# 8x8_LED_Cathode_Base_V4.net
KiCad netlist of a schematic drawn in EAGLE
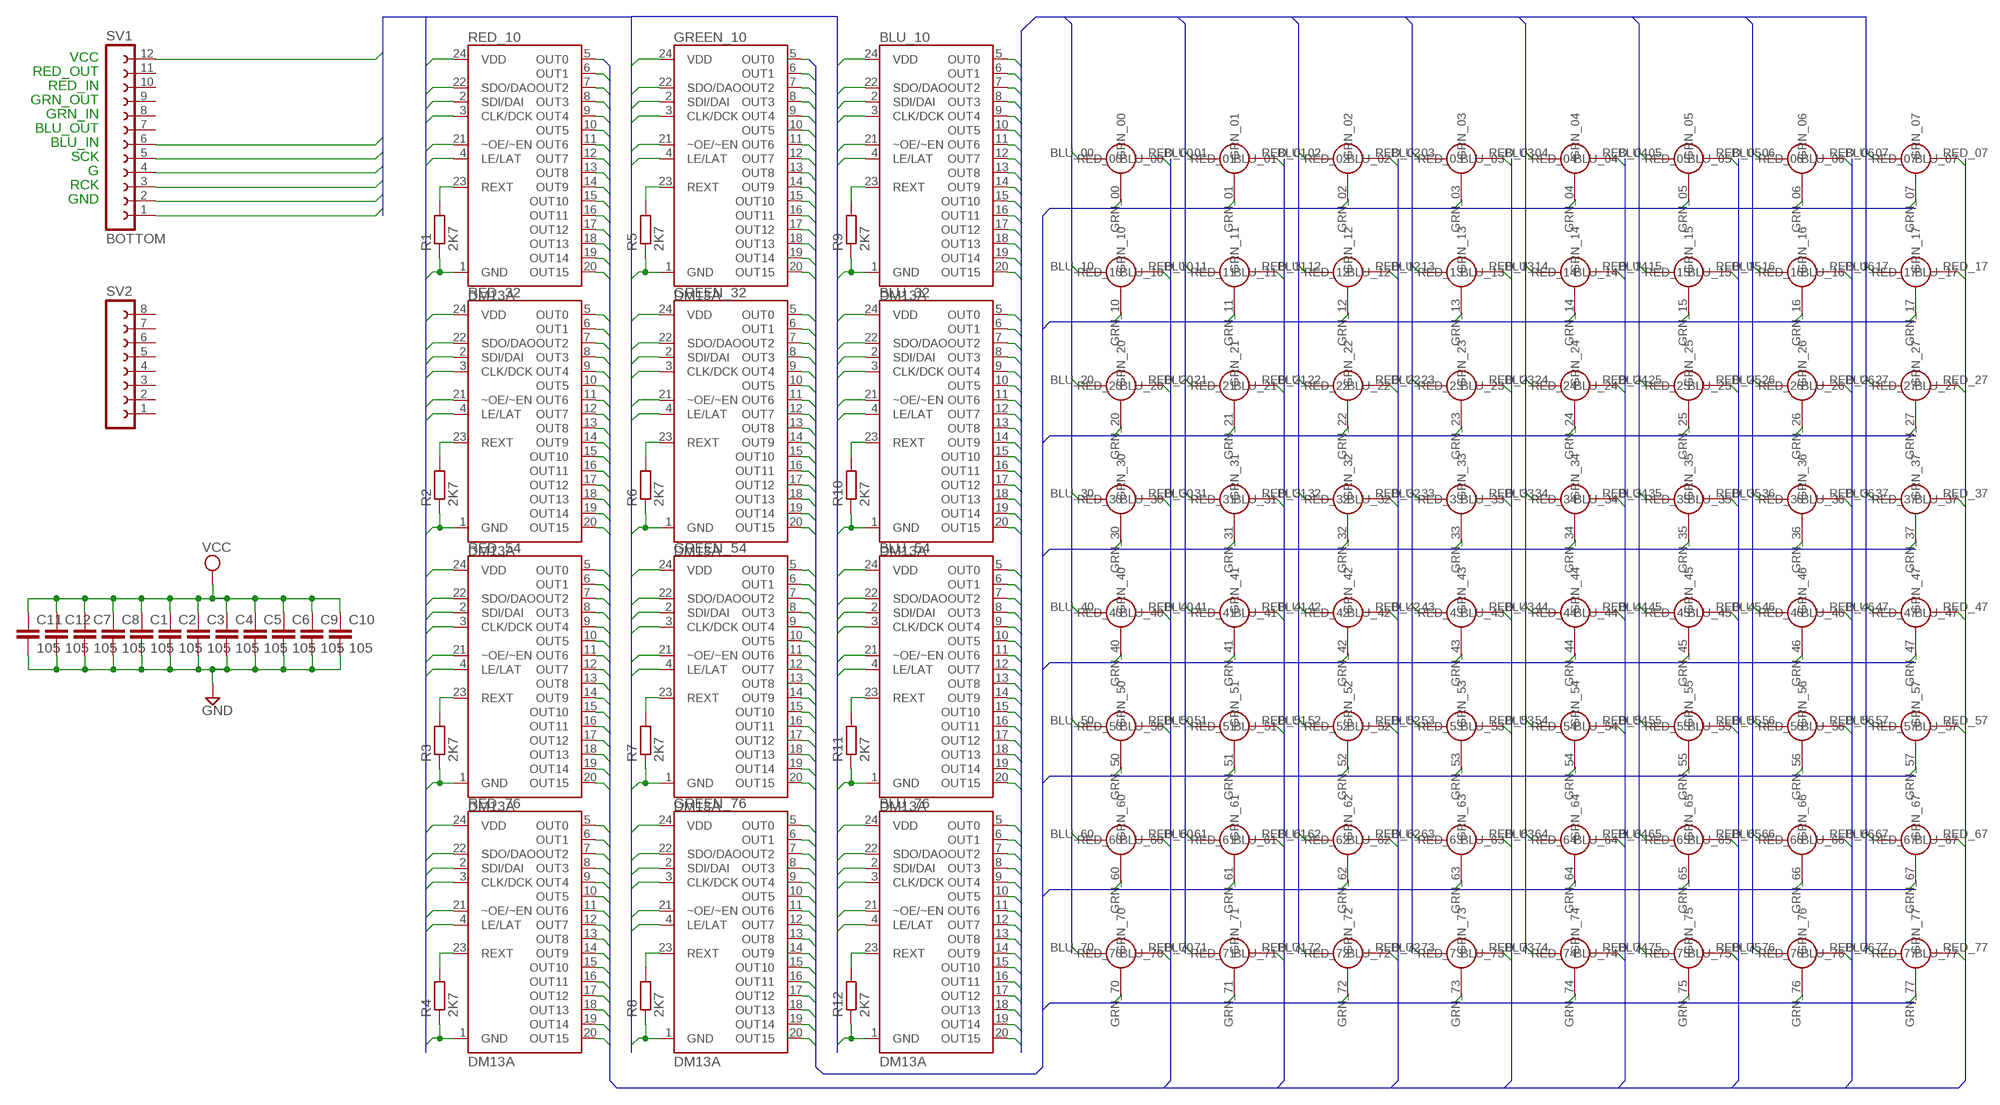
[diagram p0: schematic, sheet 1]

(export (version "E")
  (design (tool "Eeschema 10.0.6"))
  (components
    (comp (ref "BLU_10")
      (value "DM13A")
      (footprint "eagle-import:DIL24-3")
      (libsource (lib "eagle-import") (part "DM13A"))
    )
    (comp (ref "BLU_32")
      (value "DM13A")
      (footprint "eagle-import:DIL24-3")
      (libsource (lib "eagle-import") (part "DM13A"))
    )
    (comp (ref "BLU_54")
      (value "DM13A")
      (footprint "eagle-import:DIL24-3")
      (libsource (lib "eagle-import") (part "DM13A"))
    )
    (comp (ref "BLU_76")
      (value "DM13A")
      (footprint "eagle-import:DIL24-3")
      (libsource (lib "eagle-import") (part "DM13A"))
    )
    (comp (ref "C1")
      (value "105")
      (footprint "eagle-import:C1206")
      (libsource (lib "eagle-import") (part "C-EUC1206"))
    )
    (comp (ref "C2")
      (value "105")
      (footprint "eagle-import:C1206")
      (libsource (lib "eagle-import") (part "C-EUC1206"))
    )
    (comp (ref "C3")
      (value "105")
      (footprint "eagle-import:C1206")
      (libsource (lib "eagle-import") (part "C-EUC1206"))
    )
    (comp (ref "C4")
      (value "105")
      (footprint "eagle-import:C1206")
      (libsource (lib "eagle-import") (part "C-EUC1206"))
    )
    (comp (ref "C5")
      (value "105")
      (footprint "eagle-import:C1206")
      (libsource (lib "eagle-import") (part "C-EUC1206"))
    )
    (comp (ref "C6")
      (value "105")
      (footprint "eagle-import:C1206")
      (libsource (lib "eagle-import") (part "C-EUC1206"))
    )
    (comp (ref "C7")
      (value "105")
      (footprint "eagle-import:C1206")
      (libsource (lib "eagle-import") (part "C-EUC1206"))
    )
    (comp (ref "C8")
      (value "105")
      (footprint "eagle-import:C1206")
      (libsource (lib "eagle-import") (part "C-EUC1206"))
    )
    (comp (ref "C9")
      (value "105")
      (footprint "eagle-import:C1206")
      (libsource (lib "eagle-import") (part "C-EUC1206"))
    )
    (comp (ref "C10")
      (value "105")
      (footprint "eagle-import:C1206")
      (libsource (lib "eagle-import") (part "C-EUC1206"))
    )
    (comp (ref "C11")
      (value "105")
      (footprint "eagle-import:C1206")
      (libsource (lib "eagle-import") (part "C-EUC1206"))
    )
    (comp (ref "C12")
      (value "105")
      (footprint "eagle-import:C1206")
      (libsource (lib "eagle-import") (part "C-EUC1206"))
    )
    (comp (ref "GREEN_10")
      (value "DM13A")
      (footprint "eagle-import:DIL24-3")
      (libsource (lib "eagle-import") (part "DM13A"))
    )
    (comp (ref "GREEN_32")
      (value "DM13A")
      (footprint "eagle-import:DIL24-3")
      (libsource (lib "eagle-import") (part "DM13A"))
    )
    (comp (ref "GREEN_54")
      (value "DM13A")
      (footprint "eagle-import:DIL24-3")
      (libsource (lib "eagle-import") (part "DM13A"))
    )
    (comp (ref "GREEN_76")
      (value "DM13A")
      (footprint "eagle-import:DIL24-3")
      (libsource (lib "eagle-import") (part "DM13A"))
    )
    (comp (ref "R1")
      (value "2K7")
      (footprint "eagle-import:R1206")
      (libsource (lib "eagle-import") (part "R-EU_R1206"))
    )
    (comp (ref "R2")
      (value "2K7")
      (footprint "eagle-import:R1206")
      (libsource (lib "eagle-import") (part "R-EU_R1206"))
    )
    (comp (ref "R3")
      (value "2K7")
      (footprint "eagle-import:R1206")
      (libsource (lib "eagle-import") (part "R-EU_R1206"))
    )
    (comp (ref "R4")
      (value "2K7")
      (footprint "eagle-import:R1206")
      (libsource (lib "eagle-import") (part "R-EU_R1206"))
    )
    (comp (ref "R5")
      (value "2K7")
      (footprint "eagle-import:R1206")
      (libsource (lib "eagle-import") (part "R-EU_R1206"))
    )
    (comp (ref "R6")
      (value "2K7")
      (footprint "eagle-import:R1206")
      (libsource (lib "eagle-import") (part "R-EU_R1206"))
    )
    (comp (ref "R7")
      (value "2K7")
      (footprint "eagle-import:R1206")
      (libsource (lib "eagle-import") (part "R-EU_R1206"))
    )
    (comp (ref "R8")
      (value "2K7")
      (footprint "eagle-import:R1206")
      (libsource (lib "eagle-import") (part "R-EU_R1206"))
    )
    (comp (ref "R9")
      (value "2K7")
      (footprint "eagle-import:R1206")
      (libsource (lib "eagle-import") (part "R-EU_R1206"))
    )
    (comp (ref "R10")
      (value "2K7")
      (footprint "eagle-import:R1206")
      (libsource (lib "eagle-import") (part "R-EU_R1206"))
    )
    (comp (ref "R11")
      (value "2K7")
      (footprint "eagle-import:R1206")
      (libsource (lib "eagle-import") (part "R-EU_R1206"))
    )
    (comp (ref "R12")
      (value "2K7")
      (footprint "eagle-import:R1206")
      (libsource (lib "eagle-import") (part "R-EU_R1206"))
    )
    (comp (ref "RED_10")
      (value "DM13A")
      (footprint "eagle-import:DIL24-3")
      (libsource (lib "eagle-import") (part "DM13A"))
    )
    (comp (ref "RED_32")
      (value "DM13A")
      (footprint "eagle-import:DIL24-3")
      (libsource (lib "eagle-import") (part "DM13A"))
    )
    (comp (ref "RED_54")
      (value "DM13A")
      (footprint "eagle-import:DIL24-3")
      (libsource (lib "eagle-import") (part "DM13A"))
    )
    (comp (ref "RED_76")
      (value "DM13A")
      (footprint "eagle-import:DIL24-3")
      (libsource (lib "eagle-import") (part "DM13A"))
    )
    (comp (ref "SV1")
      (value "BOTTOM")
      (footprint "eagle-import:FE12")
      (libsource (lib "eagle-import") (part "FE12-1"))
    )
    (comp (ref "SV2")
      (value "FE08-1")
      (footprint "eagle-import:FE08")
      (libsource (lib "eagle-import") (part "FE08-1"))
    )
    (comp (ref "U$1")
      (value "8X8_RGB_COLUMN")
      (footprint "eagle-import:8X8_RGB_LED_120")
      (libsource (lib "eagle-import") (part "8X8_RGB_COLUMN"))
    )
  )
  (nets
    (net (code "2") (name "/BLANK") (class "Default")
      (node (ref "BLU_10") (pin "21") (pinfunction "~{OE/}EN_21") (pintype "bidirectional"))
      (node (ref "BLU_32") (pin "21") (pinfunction "~{OE/}EN_21") (pintype "bidirectional"))
      (node (ref "BLU_54") (pin "21") (pinfunction "~{OE/}EN_21") (pintype "bidirectional"))
      (node (ref "BLU_76") (pin "21") (pinfunction "~{OE/}EN_21") (pintype "bidirectional"))
      (node (ref "GREEN_10") (pin "21") (pinfunction "~{OE/}EN_21") (pintype "bidirectional"))
      (node (ref "GREEN_32") (pin "21") (pinfunction "~{OE/}EN_21") (pintype "bidirectional"))
      (node (ref "GREEN_54") (pin "21") (pinfunction "~{OE/}EN_21") (pintype "bidirectional"))
      (node (ref "GREEN_76") (pin "21") (pinfunction "~{OE/}EN_21") (pintype "bidirectional"))
      (node (ref "RED_10") (pin "21") (pinfunction "~{OE/}EN_21") (pintype "bidirectional"))
      (node (ref "RED_32") (pin "21") (pinfunction "~{OE/}EN_21") (pintype "bidirectional"))
      (node (ref "RED_54") (pin "21") (pinfunction "~{OE/}EN_21") (pintype "bidirectional"))
      (node (ref "RED_76") (pin "21") (pinfunction "~{OE/}EN_21") (pintype "bidirectional"))
      (node (ref "SV1") (pin "4") (pinfunction "4_4") (pintype "passive"))
    )
    (net (code "3") (name "/BLU_00") (class "Default")
      (node (ref "BLU_10") (pin "5") (pinfunction "OUT0_5") (pintype "bidirectional"))
      (node (ref "U$1") (pin "BLU_00") (pinfunction "BLU_00_BLU_00") (pintype "bidirectional"))
    )
    (net (code "4") (name "/BLU_01") (class "Default")
      (node (ref "BLU_10") (pin "6") (pinfunction "OUT1_6") (pintype "bidirectional"))
      (node (ref "U$1") (pin "BLU_01") (pinfunction "BLU_01_BLU_01") (pintype "bidirectional"))
    )
    (net (code "5") (name "/BLU_02") (class "Default")
      (node (ref "BLU_10") (pin "7") (pinfunction "OUT2_7") (pintype "bidirectional"))
      (node (ref "U$1") (pin "BLU_02") (pinfunction "BLU_02_BLU_02") (pintype "bidirectional"))
    )
    (net (code "6") (name "/BLU_03") (class "Default")
      (node (ref "BLU_10") (pin "8") (pinfunction "OUT3_8") (pintype "bidirectional"))
      (node (ref "U$1") (pin "BLU_03") (pinfunction "BLU_03_BLU_03") (pintype "bidirectional"))
    )
    (net (code "7") (name "/BLU_04") (class "Default")
      (node (ref "BLU_10") (pin "9") (pinfunction "OUT4_9") (pintype "bidirectional"))
      (node (ref "U$1") (pin "BLU_04") (pinfunction "BLU_04_BLU_04") (pintype "bidirectional"))
    )
    (net (code "8") (name "/BLU_05") (class "Default")
      (node (ref "BLU_10") (pin "10") (pinfunction "OUT5_10") (pintype "bidirectional"))
      (node (ref "U$1") (pin "BLU_05") (pinfunction "BLU_05_BLU_05") (pintype "bidirectional"))
    )
    (net (code "9") (name "/BLU_06") (class "Default")
      (node (ref "BLU_10") (pin "11") (pinfunction "OUT6_11") (pintype "bidirectional"))
      (node (ref "U$1") (pin "BLU_06") (pinfunction "BLU_06_BLU_06") (pintype "bidirectional"))
    )
    (net (code "10") (name "/BLU_07") (class "Default")
      (node (ref "BLU_10") (pin "12") (pinfunction "OUT7_12") (pintype "bidirectional"))
      (node (ref "U$1") (pin "BLU_07") (pinfunction "BLU_07_BLU_07") (pintype "bidirectional"))
    )
    (net (code "11") (name "/BLU_10") (class "Default")
      (node (ref "BLU_10") (pin "13") (pinfunction "OUT8_13") (pintype "bidirectional"))
      (node (ref "U$1") (pin "BLU_10") (pinfunction "BLU_10_BLU_10") (pintype "bidirectional"))
    )
    (net (code "12") (name "/BLU_11") (class "Default")
      (node (ref "BLU_10") (pin "14") (pinfunction "OUT9_14") (pintype "bidirectional"))
      (node (ref "U$1") (pin "BLU_11") (pinfunction "BLU_11_BLU_11") (pintype "bidirectional"))
    )
    (net (code "13") (name "/BLU_12") (class "Default")
      (node (ref "BLU_10") (pin "15") (pinfunction "OUT10_15") (pintype "bidirectional"))
      (node (ref "U$1") (pin "BLU_12") (pinfunction "BLU_12_BLU_12") (pintype "bidirectional"))
    )
    (net (code "14") (name "/BLU_13") (class "Default")
      (node (ref "BLU_10") (pin "16") (pinfunction "OUT11_16") (pintype "bidirectional"))
      (node (ref "U$1") (pin "BLU_13") (pinfunction "BLU_13_BLU_13") (pintype "bidirectional"))
    )
    (net (code "15") (name "/BLU_14") (class "Default")
      (node (ref "BLU_10") (pin "17") (pinfunction "OUT12_17") (pintype "bidirectional"))
      (node (ref "U$1") (pin "BLU_14") (pinfunction "BLU_14_BLU_14") (pintype "bidirectional"))
    )
    (net (code "16") (name "/BLU_15") (class "Default")
      (node (ref "BLU_10") (pin "18") (pinfunction "OUT13_18") (pintype "bidirectional"))
      (node (ref "U$1") (pin "BLU_15") (pinfunction "BLU_15_BLU_15") (pintype "bidirectional"))
    )
    (net (code "17") (name "/BLU_16") (class "Default")
      (node (ref "BLU_10") (pin "19") (pinfunction "OUT14_19") (pintype "bidirectional"))
      (node (ref "U$1") (pin "BLU_16") (pinfunction "BLU_16_BLU_16") (pintype "bidirectional"))
    )
    (net (code "18") (name "/BLU_17") (class "Default")
      (node (ref "BLU_10") (pin "20") (pinfunction "OUT15_20") (pintype "bidirectional"))
      (node (ref "U$1") (pin "BLU_17") (pinfunction "BLU_17_BLU_17") (pintype "bidirectional"))
    )
    (net (code "19") (name "/BLU_20") (class "Default")
      (node (ref "BLU_32") (pin "5") (pinfunction "OUT0_5") (pintype "bidirectional"))
      (node (ref "U$1") (pin "BLU_20") (pinfunction "BLU_20_BLU_20") (pintype "bidirectional"))
    )
    (net (code "20") (name "/BLU_21") (class "Default")
      (node (ref "BLU_32") (pin "6") (pinfunction "OUT1_6") (pintype "bidirectional"))
      (node (ref "U$1") (pin "BLU_21") (pinfunction "BLU_21_BLU_21") (pintype "bidirectional"))
    )
    (net (code "21") (name "/BLU_22") (class "Default")
      (node (ref "BLU_32") (pin "7") (pinfunction "OUT2_7") (pintype "bidirectional"))
      (node (ref "U$1") (pin "BLU_22") (pinfunction "BLU_22_BLU_22") (pintype "bidirectional"))
    )
    (net (code "22") (name "/BLU_23") (class "Default")
      (node (ref "BLU_32") (pin "8") (pinfunction "OUT3_8") (pintype "bidirectional"))
      (node (ref "U$1") (pin "BLU_23") (pinfunction "BLU_23_BLU_23") (pintype "bidirectional"))
    )
    (net (code "23") (name "/BLU_24") (class "Default")
      (node (ref "BLU_32") (pin "9") (pinfunction "OUT4_9") (pintype "bidirectional"))
      (node (ref "U$1") (pin "BLU_24") (pinfunction "BLU_24_BLU_24") (pintype "bidirectional"))
    )
    (net (code "24") (name "/BLU_25") (class "Default")
      (node (ref "BLU_32") (pin "10") (pinfunction "OUT5_10") (pintype "bidirectional"))
      (node (ref "U$1") (pin "BLU_25") (pinfunction "BLU_25_BLU_25") (pintype "bidirectional"))
    )
    (net (code "25") (name "/BLU_26") (class "Default")
      (node (ref "BLU_32") (pin "11") (pinfunction "OUT6_11") (pintype "bidirectional"))
      (node (ref "U$1") (pin "BLU_26") (pinfunction "BLU_26_BLU_26") (pintype "bidirectional"))
    )
    (net (code "26") (name "/BLU_27") (class "Default")
      (node (ref "BLU_32") (pin "12") (pinfunction "OUT7_12") (pintype "bidirectional"))
      (node (ref "U$1") (pin "BLU_27") (pinfunction "BLU_27_BLU_27") (pintype "bidirectional"))
    )
    (net (code "27") (name "/BLU_30") (class "Default")
      (node (ref "BLU_32") (pin "13") (pinfunction "OUT8_13") (pintype "bidirectional"))
      (node (ref "U$1") (pin "BLU_30") (pinfunction "BLU_30_BLU_30") (pintype "bidirectional"))
    )
    (net (code "28") (name "/BLU_31") (class "Default")
      (node (ref "BLU_32") (pin "14") (pinfunction "OUT9_14") (pintype "bidirectional"))
      (node (ref "U$1") (pin "BLU_31") (pinfunction "BLU_31_BLU_31") (pintype "bidirectional"))
    )
    (net (code "29") (name "/BLU_32") (class "Default")
      (node (ref "BLU_32") (pin "15") (pinfunction "OUT10_15") (pintype "bidirectional"))
      (node (ref "U$1") (pin "BLU_32") (pinfunction "BLU_32_BLU_32") (pintype "bidirectional"))
    )
    (net (code "30") (name "/BLU_32_DATA") (class "Default")
      (node (ref "BLU_10") (pin "22") (pinfunction "SDO/DAO_22") (pintype "bidirectional"))
      (node (ref "BLU_32") (pin "2") (pinfunction "SDI/DAI_2") (pintype "bidirectional"))
    )
    (net (code "31") (name "/BLU_33") (class "Default")
      (node (ref "BLU_32") (pin "16") (pinfunction "OUT11_16") (pintype "bidirectional"))
      (node (ref "U$1") (pin "BLU_33") (pinfunction "BLU_33_BLU_33") (pintype "bidirectional"))
    )
    (net (code "32") (name "/BLU_34") (class "Default")
      (node (ref "BLU_32") (pin "17") (pinfunction "OUT12_17") (pintype "bidirectional"))
      (node (ref "U$1") (pin "BLU_34") (pinfunction "BLU_34_BLU_34") (pintype "bidirectional"))
    )
    (net (code "33") (name "/BLU_35") (class "Default")
      (node (ref "BLU_32") (pin "18") (pinfunction "OUT13_18") (pintype "bidirectional"))
      (node (ref "U$1") (pin "BLU_35") (pinfunction "BLU_35_BLU_35") (pintype "bidirectional"))
    )
    (net (code "34") (name "/BLU_36") (class "Default")
      (node (ref "BLU_32") (pin "19") (pinfunction "OUT14_19") (pintype "bidirectional"))
      (node (ref "U$1") (pin "BLU_36") (pinfunction "BLU_36_BLU_36") (pintype "bidirectional"))
    )
    (net (code "35") (name "/BLU_37") (class "Default")
      (node (ref "BLU_32") (pin "20") (pinfunction "OUT15_20") (pintype "bidirectional"))
      (node (ref "U$1") (pin "BLU_37") (pinfunction "BLU_37_BLU_37") (pintype "bidirectional"))
    )
    (net (code "36") (name "/BLU_40") (class "Default")
      (node (ref "BLU_54") (pin "5") (pinfunction "OUT0_5") (pintype "bidirectional"))
      (node (ref "U$1") (pin "BLU_40") (pinfunction "BLU_40_BLU_40") (pintype "bidirectional"))
    )
    (net (code "37") (name "/BLU_41") (class "Default")
      (node (ref "BLU_54") (pin "6") (pinfunction "OUT1_6") (pintype "bidirectional"))
      (node (ref "U$1") (pin "BLU_41") (pinfunction "BLU_41_BLU_41") (pintype "bidirectional"))
    )
    (net (code "38") (name "/BLU_42") (class "Default")
      (node (ref "BLU_54") (pin "7") (pinfunction "OUT2_7") (pintype "bidirectional"))
      (node (ref "U$1") (pin "BLU_42") (pinfunction "BLU_42_BLU_42") (pintype "bidirectional"))
    )
    (net (code "39") (name "/BLU_43") (class "Default")
      (node (ref "BLU_54") (pin "8") (pinfunction "OUT3_8") (pintype "bidirectional"))
      (node (ref "U$1") (pin "BLU_43") (pinfunction "BLU_43_BLU_43") (pintype "bidirectional"))
    )
    (net (code "40") (name "/BLU_44") (class "Default")
      (node (ref "BLU_54") (pin "9") (pinfunction "OUT4_9") (pintype "bidirectional"))
      (node (ref "U$1") (pin "BLU_44") (pinfunction "BLU_44_BLU_44") (pintype "bidirectional"))
    )
    (net (code "41") (name "/BLU_45") (class "Default")
      (node (ref "BLU_54") (pin "10") (pinfunction "OUT5_10") (pintype "bidirectional"))
      (node (ref "U$1") (pin "BLU_45") (pinfunction "BLU_45_BLU_45") (pintype "bidirectional"))
    )
    (net (code "42") (name "/BLU_46") (class "Default")
      (node (ref "BLU_54") (pin "11") (pinfunction "OUT6_11") (pintype "bidirectional"))
      (node (ref "U$1") (pin "BLU_46") (pinfunction "BLU_46_BLU_46") (pintype "bidirectional"))
    )
    (net (code "43") (name "/BLU_47") (class "Default")
      (node (ref "BLU_54") (pin "12") (pinfunction "OUT7_12") (pintype "bidirectional"))
      (node (ref "U$1") (pin "BLU_47") (pinfunction "BLU_47_BLU_47") (pintype "bidirectional"))
    )
    (net (code "44") (name "/BLU_50") (class "Default")
      (node (ref "BLU_54") (pin "13") (pinfunction "OUT8_13") (pintype "bidirectional"))
      (node (ref "U$1") (pin "BLU_50") (pinfunction "BLU_50_BLU_50") (pintype "bidirectional"))
    )
    (net (code "45") (name "/BLU_51") (class "Default")
      (node (ref "BLU_54") (pin "14") (pinfunction "OUT9_14") (pintype "bidirectional"))
      (node (ref "U$1") (pin "BLU_51") (pinfunction "BLU_51_BLU_51") (pintype "bidirectional"))
    )
    (net (code "46") (name "/BLU_52") (class "Default")
      (node (ref "BLU_54") (pin "15") (pinfunction "OUT10_15") (pintype "bidirectional"))
      (node (ref "U$1") (pin "BLU_52") (pinfunction "BLU_52_BLU_52") (pintype "bidirectional"))
    )
    (net (code "47") (name "/BLU_53") (class "Default")
      (node (ref "BLU_54") (pin "16") (pinfunction "OUT11_16") (pintype "bidirectional"))
      (node (ref "U$1") (pin "BLU_53") (pinfunction "BLU_53_BLU_53") (pintype "bidirectional"))
    )
    (net (code "48") (name "/BLU_54") (class "Default")
      (node (ref "BLU_54") (pin "17") (pinfunction "OUT12_17") (pintype "bidirectional"))
      (node (ref "U$1") (pin "BLU_54") (pinfunction "BLU_54_BLU_54") (pintype "bidirectional"))
    )
    (net (code "49") (name "/BLU_54_DATA") (class "Default")
      (node (ref "BLU_32") (pin "22") (pinfunction "SDO/DAO_22") (pintype "bidirectional"))
      (node (ref "BLU_54") (pin "2") (pinfunction "SDI/DAI_2") (pintype "bidirectional"))
    )
    (net (code "50") (name "/BLU_55") (class "Default")
      (node (ref "BLU_54") (pin "18") (pinfunction "OUT13_18") (pintype "bidirectional"))
      (node (ref "U$1") (pin "BLU_55") (pinfunction "BLU_55_BLU_55") (pintype "bidirectional"))
    )
    (net (code "51") (name "/BLU_56") (class "Default")
      (node (ref "BLU_54") (pin "19") (pinfunction "OUT14_19") (pintype "bidirectional"))
      (node (ref "U$1") (pin "BLU_56") (pinfunction "BLU_56_BLU_56") (pintype "bidirectional"))
    )
    (net (code "52") (name "/BLU_57") (class "Default")
      (node (ref "BLU_54") (pin "20") (pinfunction "OUT15_20") (pintype "bidirectional"))
      (node (ref "U$1") (pin "BLU_57") (pinfunction "BLU_57_BLU_57") (pintype "bidirectional"))
    )
    (net (code "53") (name "/BLU_60") (class "Default")
      (node (ref "BLU_76") (pin "5") (pinfunction "OUT0_5") (pintype "bidirectional"))
      (node (ref "U$1") (pin "BLU_60") (pinfunction "BLU_60_BLU_60") (pintype "bidirectional"))
    )
    (net (code "54") (name "/BLU_61") (class "Default")
      (node (ref "BLU_76") (pin "6") (pinfunction "OUT1_6") (pintype "bidirectional"))
      (node (ref "U$1") (pin "BLU_61") (pinfunction "BLU_61_BLU_61") (pintype "bidirectional"))
    )
    (net (code "55") (name "/BLU_62") (class "Default")
      (node (ref "BLU_76") (pin "7") (pinfunction "OUT2_7") (pintype "bidirectional"))
      (node (ref "U$1") (pin "BLU_62") (pinfunction "BLU_62_BLU_62") (pintype "bidirectional"))
    )
    (net (code "56") (name "/BLU_63") (class "Default")
      (node (ref "BLU_76") (pin "8") (pinfunction "OUT3_8") (pintype "bidirectional"))
      (node (ref "U$1") (pin "BLU_63") (pinfunction "BLU_63_BLU_63") (pintype "bidirectional"))
    )
    (net (code "57") (name "/BLU_64") (class "Default")
      (node (ref "BLU_76") (pin "9") (pinfunction "OUT4_9") (pintype "bidirectional"))
      (node (ref "U$1") (pin "BLU_64") (pinfunction "BLU_64_BLU_64") (pintype "bidirectional"))
    )
    (net (code "58") (name "/BLU_65") (class "Default")
      (node (ref "BLU_76") (pin "10") (pinfunction "OUT5_10") (pintype "bidirectional"))
      (node (ref "U$1") (pin "BLU_65") (pinfunction "BLU_65_BLU_65") (pintype "bidirectional"))
    )
    (net (code "59") (name "/BLU_66") (class "Default")
      (node (ref "BLU_76") (pin "11") (pinfunction "OUT6_11") (pintype "bidirectional"))
      (node (ref "U$1") (pin "BLU_66") (pinfunction "BLU_66_BLU_66") (pintype "bidirectional"))
    )
    (net (code "60") (name "/BLU_67") (class "Default")
      (node (ref "BLU_76") (pin "12") (pinfunction "OUT7_12") (pintype "bidirectional"))
      (node (ref "U$1") (pin "BLU_67") (pinfunction "BLU_67_BLU_67") (pintype "bidirectional"))
    )
    (net (code "61") (name "/BLU_70") (class "Default")
      (node (ref "BLU_76") (pin "13") (pinfunction "OUT8_13") (pintype "bidirectional"))
      (node (ref "U$1") (pin "BLU_70") (pinfunction "BLU_70_BLU_70") (pintype "bidirectional"))
    )
    (net (code "62") (name "/BLU_71") (class "Default")
      (node (ref "BLU_76") (pin "14") (pinfunction "OUT9_14") (pintype "bidirectional"))
      (node (ref "U$1") (pin "BLU_71") (pinfunction "BLU_71_BLU_71") (pintype "bidirectional"))
    )
    (net (code "63") (name "/BLU_72") (class "Default")
      (node (ref "BLU_76") (pin "15") (pinfunction "OUT10_15") (pintype "bidirectional"))
      (node (ref "U$1") (pin "BLU_72") (pinfunction "BLU_72_BLU_72") (pintype "bidirectional"))
    )
    (net (code "64") (name "/BLU_73") (class "Default")
      (node (ref "BLU_76") (pin "16") (pinfunction "OUT11_16") (pintype "bidirectional"))
      (node (ref "U$1") (pin "BLU_73") (pinfunction "BLU_73_BLU_73") (pintype "bidirectional"))
    )
    (net (code "65") (name "/BLU_74") (class "Default")
      (node (ref "BLU_76") (pin "17") (pinfunction "OUT12_17") (pintype "bidirectional"))
      (node (ref "U$1") (pin "BLU_74") (pinfunction "BLU_74_BLU_74") (pintype "bidirectional"))
    )
    (net (code "66") (name "/BLU_75") (class "Default")
      (node (ref "BLU_76") (pin "18") (pinfunction "OUT13_18") (pintype "bidirectional"))
      (node (ref "U$1") (pin "BLU_75") (pinfunction "BLU_75_BLU_75") (pintype "bidirectional"))
    )
    (net (code "67") (name "/BLU_76") (class "Default")
      (node (ref "BLU_76") (pin "19") (pinfunction "OUT14_19") (pintype "bidirectional"))
      (node (ref "U$1") (pin "BLU_76") (pinfunction "BLU_76_BLU_76") (pintype "bidirectional"))
    )
    (net (code "68") (name "/BLU_76_DATA") (class "Default")
      (node (ref "BLU_54") (pin "22") (pinfunction "SDO/DAO_22") (pintype "bidirectional"))
      (node (ref "BLU_76") (pin "2") (pinfunction "SDI/DAI_2") (pintype "bidirectional"))
    )
    (net (code "69") (name "/BLU_77") (class "Default")
      (node (ref "BLU_76") (pin "20") (pinfunction "OUT15_20") (pintype "bidirectional"))
      (node (ref "U$1") (pin "BLU_77") (pinfunction "BLU_77_BLU_77") (pintype "bidirectional"))
    )
    (net (code "70") (name "/BLU_IN") (class "Default")
      (node (ref "BLU_10") (pin "2") (pinfunction "SDI/DAI_2") (pintype "bidirectional"))
      (node (ref "SV1") (pin "6") (pinfunction "6_6") (pintype "passive"))
    )
    (net (code "71") (name "/BLU_OUT") (class "Default")
      (node (ref "BLU_76") (pin "22") (pinfunction "SDO/DAO_22") (pintype "bidirectional"))
      (node (ref "GREEN_10") (pin "2") (pinfunction "SDI/DAI_2") (pintype "bidirectional"))
    )
    (net (code "72") (name "/CLOCK") (class "Default")
      (node (ref "BLU_10") (pin "3") (pinfunction "CLK/DCK_3") (pintype "bidirectional"))
      (node (ref "BLU_32") (pin "3") (pinfunction "CLK/DCK_3") (pintype "bidirectional"))
      (node (ref "BLU_54") (pin "3") (pinfunction "CLK/DCK_3") (pintype "bidirectional"))
      (node (ref "BLU_76") (pin "3") (pinfunction "CLK/DCK_3") (pintype "bidirectional"))
      (node (ref "GREEN_10") (pin "3") (pinfunction "CLK/DCK_3") (pintype "bidirectional"))
      (node (ref "GREEN_32") (pin "3") (pinfunction "CLK/DCK_3") (pintype "bidirectional"))
      (node (ref "GREEN_54") (pin "3") (pinfunction "CLK/DCK_3") (pintype "bidirectional"))
      (node (ref "GREEN_76") (pin "3") (pinfunction "CLK/DCK_3") (pintype "bidirectional"))
      (node (ref "RED_10") (pin "3") (pinfunction "CLK/DCK_3") (pintype "bidirectional"))
      (node (ref "RED_32") (pin "3") (pinfunction "CLK/DCK_3") (pintype "bidirectional"))
      (node (ref "RED_54") (pin "3") (pinfunction "CLK/DCK_3") (pintype "bidirectional"))
      (node (ref "RED_76") (pin "3") (pinfunction "CLK/DCK_3") (pintype "bidirectional"))
      (node (ref "SV1") (pin "5") (pinfunction "5_5") (pintype "passive"))
    )
    (net (code "73") (name "/GRN_00") (class "Default")
      (node (ref "GREEN_10") (pin "5") (pinfunction "OUT0_5") (pintype "bidirectional"))
      (node (ref "U$1") (pin "GRN_00") (pinfunction "GRN_00_GRN_00") (pintype "bidirectional"))
    )
    (net (code "74") (name "/GRN_01") (class "Default")
      (node (ref "GREEN_10") (pin "6") (pinfunction "OUT1_6") (pintype "bidirectional"))
      (node (ref "U$1") (pin "GRN_01") (pinfunction "GRN_01_GRN_01") (pintype "bidirectional"))
    )
    (net (code "75") (name "/GRN_02") (class "Default")
      (node (ref "GREEN_10") (pin "7") (pinfunction "OUT2_7") (pintype "bidirectional"))
      (node (ref "U$1") (pin "GRN_02") (pinfunction "GRN_02_GRN_02") (pintype "bidirectional"))
    )
    (net (code "76") (name "/GRN_03") (class "Default")
      (node (ref "GREEN_10") (pin "8") (pinfunction "OUT3_8") (pintype "bidirectional"))
      (node (ref "U$1") (pin "GRN_03") (pinfunction "GRN_03_GRN_03") (pintype "bidirectional"))
    )
    (net (code "77") (name "/GRN_04") (class "Default")
      (node (ref "GREEN_10") (pin "9") (pinfunction "OUT4_9") (pintype "bidirectional"))
      (node (ref "U$1") (pin "GRN_04") (pinfunction "GRN_04_GRN_04") (pintype "bidirectional"))
    )
    (net (code "78") (name "/GRN_05") (class "Default")
      (node (ref "GREEN_10") (pin "10") (pinfunction "OUT5_10") (pintype "bidirectional"))
      (node (ref "U$1") (pin "GRN_05") (pinfunction "GRN_05_GRN_05") (pintype "bidirectional"))
    )
    (net (code "79") (name "/GRN_06") (class "Default")
      (node (ref "GREEN_10") (pin "11") (pinfunction "OUT6_11") (pintype "bidirectional"))
      (node (ref "U$1") (pin "GRN_06") (pinfunction "GRN_06_GRN_06") (pintype "bidirectional"))
    )
    (net (code "80") (name "/GRN_07") (class "Default")
      (node (ref "GREEN_10") (pin "12") (pinfunction "OUT7_12") (pintype "bidirectional"))
      (node (ref "U$1") (pin "GRN_07") (pinfunction "GRN_07_GRN_07") (pintype "bidirectional"))
    )
    (net (code "81") (name "/GRN_10") (class "Default")
      (node (ref "GREEN_10") (pin "13") (pinfunction "OUT8_13") (pintype "bidirectional"))
      (node (ref "U$1") (pin "GRN_10") (pinfunction "GRN_10_GRN_10") (pintype "bidirectional"))
    )
    (net (code "82") (name "/GRN_11") (class "Default")
      (node (ref "GREEN_10") (pin "14") (pinfunction "OUT9_14") (pintype "bidirectional"))
      (node (ref "U$1") (pin "GRN_11") (pinfunction "GRN_11_GRN_11") (pintype "bidirectional"))
    )
    (net (code "83") (name "/GRN_12") (class "Default")
      (node (ref "GREEN_10") (pin "15") (pinfunction "OUT10_15") (pintype "bidirectional"))
      (node (ref "U$1") (pin "GRN_12") (pinfunction "GRN_12_GRN_12") (pintype "bidirectional"))
    )
    (net (code "84") (name "/GRN_13") (class "Default")
      (node (ref "GREEN_10") (pin "16") (pinfunction "OUT11_16") (pintype "bidirectional"))
      (node (ref "U$1") (pin "GRN_13") (pinfunction "GRN_13_GRN_13") (pintype "bidirectional"))
    )
    (net (code "85") (name "/GRN_14") (class "Default")
      (node (ref "GREEN_10") (pin "17") (pinfunction "OUT12_17") (pintype "bidirectional"))
      (node (ref "U$1") (pin "GRN_14") (pinfunction "GRN_14_GRN_14") (pintype "bidirectional"))
    )
    (net (code "86") (name "/GRN_15") (class "Default")
      (node (ref "GREEN_10") (pin "18") (pinfunction "OUT13_18") (pintype "bidirectional"))
      (node (ref "U$1") (pin "GRN_15") (pinfunction "GRN_15_GRN_15") (pintype "bidirectional"))
    )
    (net (code "87") (name "/GRN_16") (class "Default")
      (node (ref "GREEN_10") (pin "19") (pinfunction "OUT14_19") (pintype "bidirectional"))
      (node (ref "U$1") (pin "GRN_16") (pinfunction "GRN_16_GRN_16") (pintype "bidirectional"))
    )
    (net (code "88") (name "/GRN_17") (class "Default")
      (node (ref "GREEN_10") (pin "20") (pinfunction "OUT15_20") (pintype "bidirectional"))
      (node (ref "U$1") (pin "GRN_17") (pinfunction "GRN_17_GRN_17") (pintype "bidirectional"))
    )
    (net (code "89") (name "/GRN_20") (class "Default")
      (node (ref "GREEN_32") (pin "5") (pinfunction "OUT0_5") (pintype "bidirectional"))
      (node (ref "U$1") (pin "GRN_20") (pinfunction "GRN_20_GRN_20") (pintype "bidirectional"))
    )
    (net (code "90") (name "/GRN_21") (class "Default")
      (node (ref "GREEN_32") (pin "6") (pinfunction "OUT1_6") (pintype "bidirectional"))
      (node (ref "U$1") (pin "GRN_21") (pinfunction "GRN_21_GRN_21") (pintype "bidirectional"))
    )
    (net (code "91") (name "/GRN_22") (class "Default")
      (node (ref "GREEN_32") (pin "7") (pinfunction "OUT2_7") (pintype "bidirectional"))
      (node (ref "U$1") (pin "GRN_22") (pinfunction "GRN_22_GRN_22") (pintype "bidirectional"))
    )
    (net (code "92") (name "/GRN_23") (class "Default")
      (node (ref "GREEN_32") (pin "8") (pinfunction "OUT3_8") (pintype "bidirectional"))
      (node (ref "U$1") (pin "GRN_23") (pinfunction "GRN_23_GRN_23") (pintype "bidirectional"))
    )
    (net (code "93") (name "/GRN_24") (class "Default")
      (node (ref "GREEN_32") (pin "9") (pinfunction "OUT4_9") (pintype "bidirectional"))
      (node (ref "U$1") (pin "GRN_24") (pinfunction "GRN_24_GRN_24") (pintype "bidirectional"))
    )
    (net (code "94") (name "/GRN_25") (class "Default")
      (node (ref "GREEN_32") (pin "10") (pinfunction "OUT5_10") (pintype "bidirectional"))
      (node (ref "U$1") (pin "GRN_25") (pinfunction "GRN_25_GRN_25") (pintype "bidirectional"))
    )
    (net (code "95") (name "/GRN_26") (class "Default")
      (node (ref "GREEN_32") (pin "11") (pinfunction "OUT6_11") (pintype "bidirectional"))
      (node (ref "U$1") (pin "GRN_26") (pinfunction "GRN_26_GRN_26") (pintype "bidirectional"))
    )
    (net (code "96") (name "/GRN_27") (class "Default")
      (node (ref "GREEN_32") (pin "12") (pinfunction "OUT7_12") (pintype "bidirectional"))
      (node (ref "U$1") (pin "GRN_27") (pinfunction "GRN_27_GRN_27") (pintype "bidirectional"))
    )
    (net (code "97") (name "/GRN_30") (class "Default")
      (node (ref "GREEN_32") (pin "13") (pinfunction "OUT8_13") (pintype "bidirectional"))
      (node (ref "U$1") (pin "GRN_30") (pinfunction "GRN_30_GRN_30") (pintype "bidirectional"))
    )
    (net (code "98") (name "/GRN_31") (class "Default")
      (node (ref "GREEN_32") (pin "14") (pinfunction "OUT9_14") (pintype "bidirectional"))
      (node (ref "U$1") (pin "GRN_31") (pinfunction "GRN_31_GRN_31") (pintype "bidirectional"))
    )
    (net (code "99") (name "/GRN_32") (class "Default")
      (node (ref "GREEN_32") (pin "15") (pinfunction "OUT10_15") (pintype "bidirectional"))
      (node (ref "U$1") (pin "GRN_32") (pinfunction "GRN_32_GRN_32") (pintype "bidirectional"))
    )
    (net (code "100") (name "/GRN_32_DATA") (class "Default")
      (node (ref "GREEN_10") (pin "22") (pinfunction "SDO/DAO_22") (pintype "bidirectional"))
      (node (ref "GREEN_32") (pin "2") (pinfunction "SDI/DAI_2") (pintype "bidirectional"))
    )
    (net (code "101") (name "/GRN_33") (class "Default")
      (node (ref "GREEN_32") (pin "16") (pinfunction "OUT11_16") (pintype "bidirectional"))
      (node (ref "U$1") (pin "GRN_33") (pinfunction "GRN_33_GRN_33") (pintype "bidirectional"))
    )
    (net (code "102") (name "/GRN_34") (class "Default")
      (node (ref "GREEN_32") (pin "17") (pinfunction "OUT12_17") (pintype "bidirectional"))
      (node (ref "U$1") (pin "GRN_34") (pinfunction "GRN_34_GRN_34") (pintype "bidirectional"))
    )
    (net (code "103") (name "/GRN_35") (class "Default")
      (node (ref "GREEN_32") (pin "18") (pinfunction "OUT13_18") (pintype "bidirectional"))
      (node (ref "U$1") (pin "GRN_35") (pinfunction "GRN_35_GRN_35") (pintype "bidirectional"))
    )
    (net (code "104") (name "/GRN_36") (class "Default")
      (node (ref "GREEN_32") (pin "19") (pinfunction "OUT14_19") (pintype "bidirectional"))
      (node (ref "U$1") (pin "GRN_36") (pinfunction "GRN_36_GRN_36") (pintype "bidirectional"))
    )
    (net (code "105") (name "/GRN_37") (class "Default")
      (node (ref "GREEN_32") (pin "20") (pinfunction "OUT15_20") (pintype "bidirectional"))
      (node (ref "U$1") (pin "GRN_37") (pinfunction "GRN_37_GRN_37") (pintype "bidirectional"))
    )
    (net (code "106") (name "/GRN_40") (class "Default")
      (node (ref "GREEN_54") (pin "5") (pinfunction "OUT0_5") (pintype "bidirectional"))
      (node (ref "U$1") (pin "GRN_40") (pinfunction "GRN_40_GRN_40") (pintype "bidirectional"))
    )
    (net (code "107") (name "/GRN_41") (class "Default")
      (node (ref "GREEN_54") (pin "6") (pinfunction "OUT1_6") (pintype "bidirectional"))
      (node (ref "U$1") (pin "GRN_41") (pinfunction "GRN_41_GRN_41") (pintype "bidirectional"))
    )
    (net (code "108") (name "/GRN_42") (class "Default")
      (node (ref "GREEN_54") (pin "7") (pinfunction "OUT2_7") (pintype "bidirectional"))
      (node (ref "U$1") (pin "GRN_42") (pinfunction "GRN_42_GRN_42") (pintype "bidirectional"))
    )
    (net (code "109") (name "/GRN_43") (class "Default")
      (node (ref "GREEN_54") (pin "8") (pinfunction "OUT3_8") (pintype "bidirectional"))
      (node (ref "U$1") (pin "GRN_43") (pinfunction "GRN_43_GRN_43") (pintype "bidirectional"))
    )
    (net (code "110") (name "/GRN_44") (class "Default")
      (node (ref "GREEN_54") (pin "9") (pinfunction "OUT4_9") (pintype "bidirectional"))
      (node (ref "U$1") (pin "GRN_44") (pinfunction "GRN_44_GRN_44") (pintype "bidirectional"))
    )
    (net (code "111") (name "/GRN_45") (class "Default")
      (node (ref "GREEN_54") (pin "10") (pinfunction "OUT5_10") (pintype "bidirectional"))
      (node (ref "U$1") (pin "GRN_45") (pinfunction "GRN_45_GRN_45") (pintype "bidirectional"))
    )
    (net (code "112") (name "/GRN_46") (class "Default")
      (node (ref "GREEN_54") (pin "11") (pinfunction "OUT6_11") (pintype "bidirectional"))
      (node (ref "U$1") (pin "GRN_46") (pinfunction "GRN_46_GRN_46") (pintype "bidirectional"))
    )
    (net (code "113") (name "/GRN_47") (class "Default")
      (node (ref "GREEN_54") (pin "12") (pinfunction "OUT7_12") (pintype "bidirectional"))
      (node (ref "U$1") (pin "GRN_47") (pinfunction "GRN_47_GRN_47") (pintype "bidirectional"))
    )
    (net (code "114") (name "/GRN_50") (class "Default")
      (node (ref "GREEN_54") (pin "13") (pinfunction "OUT8_13") (pintype "bidirectional"))
      (node (ref "U$1") (pin "GRN_50") (pinfunction "GRN_50_GRN_50") (pintype "bidirectional"))
    )
    (net (code "115") (name "/GRN_51") (class "Default")
      (node (ref "GREEN_54") (pin "14") (pinfunction "OUT9_14") (pintype "bidirectional"))
      (node (ref "U$1") (pin "GRN_51") (pinfunction "GRN_51_GRN_51") (pintype "bidirectional"))
    )
    (net (code "116") (name "/GRN_52") (class "Default")
      (node (ref "GREEN_54") (pin "15") (pinfunction "OUT10_15") (pintype "bidirectional"))
      (node (ref "U$1") (pin "GRN_52") (pinfunction "GRN_52_GRN_52") (pintype "bidirectional"))
    )
    (net (code "117") (name "/GRN_53") (class "Default")
      (node (ref "GREEN_54") (pin "16") (pinfunction "OUT11_16") (pintype "bidirectional"))
      (node (ref "U$1") (pin "GRN_53") (pinfunction "GRN_53_GRN_53") (pintype "bidirectional"))
    )
    (net (code "118") (name "/GRN_54") (class "Default")
      (node (ref "GREEN_54") (pin "17") (pinfunction "OUT12_17") (pintype "bidirectional"))
      (node (ref "U$1") (pin "GRN_54") (pinfunction "GRN_54_GRN_54") (pintype "bidirectional"))
    )
    (net (code "119") (name "/GRN_54_DATA") (class "Default")
      (node (ref "GREEN_32") (pin "22") (pinfunction "SDO/DAO_22") (pintype "bidirectional"))
      (node (ref "GREEN_54") (pin "2") (pinfunction "SDI/DAI_2") (pintype "bidirectional"))
    )
    (net (code "120") (name "/GRN_55") (class "Default")
      (node (ref "GREEN_54") (pin "18") (pinfunction "OUT13_18") (pintype "bidirectional"))
      (node (ref "U$1") (pin "GRN_55") (pinfunction "GRN_55_GRN_55") (pintype "bidirectional"))
    )
    (net (code "121") (name "/GRN_56") (class "Default")
      (node (ref "GREEN_54") (pin "19") (pinfunction "OUT14_19") (pintype "bidirectional"))
      (node (ref "U$1") (pin "GRN_56") (pinfunction "GRN_56_GRN_56") (pintype "bidirectional"))
    )
    (net (code "122") (name "/GRN_57") (class "Default")
      (node (ref "GREEN_54") (pin "20") (pinfunction "OUT15_20") (pintype "bidirectional"))
      (node (ref "U$1") (pin "GRN_57") (pinfunction "GRN_57_GRN_57") (pintype "bidirectional"))
    )
    (net (code "123") (name "/GRN_60") (class "Default")
      (node (ref "GREEN_76") (pin "5") (pinfunction "OUT0_5") (pintype "bidirectional"))
      (node (ref "U$1") (pin "GRN_60") (pinfunction "GRN_60_GRN_60") (pintype "bidirectional"))
    )
    (net (code "124") (name "/GRN_61") (class "Default")
      (node (ref "GREEN_76") (pin "6") (pinfunction "OUT1_6") (pintype "bidirectional"))
      (node (ref "U$1") (pin "GRN_61") (pinfunction "GRN_61_GRN_61") (pintype "bidirectional"))
    )
    (net (code "125") (name "/GRN_62") (class "Default")
      (node (ref "GREEN_76") (pin "7") (pinfunction "OUT2_7") (pintype "bidirectional"))
      (node (ref "U$1") (pin "GRN_62") (pinfunction "GRN_62_GRN_62") (pintype "bidirectional"))
    )
    (net (code "126") (name "/GRN_63") (class "Default")
      (node (ref "GREEN_76") (pin "8") (pinfunction "OUT3_8") (pintype "bidirectional"))
      (node (ref "U$1") (pin "GRN_63") (pinfunction "GRN_63_GRN_63") (pintype "bidirectional"))
    )
    (net (code "127") (name "/GRN_64") (class "Default")
      (node (ref "GREEN_76") (pin "9") (pinfunction "OUT4_9") (pintype "bidirectional"))
      (node (ref "U$1") (pin "GRN_64") (pinfunction "GRN_64_GRN_64") (pintype "bidirectional"))
    )
    (net (code "128") (name "/GRN_65") (class "Default")
      (node (ref "GREEN_76") (pin "10") (pinfunction "OUT5_10") (pintype "bidirectional"))
      (node (ref "U$1") (pin "GRN_65") (pinfunction "GRN_65_GRN_65") (pintype "bidirectional"))
    )
    (net (code "129") (name "/GRN_66") (class "Default")
      (node (ref "GREEN_76") (pin "11") (pinfunction "OUT6_11") (pintype "bidirectional"))
      (node (ref "U$1") (pin "GRN_66") (pinfunction "GRN_66_GRN_66") (pintype "bidirectional"))
    )
    (net (code "130") (name "/GRN_67") (class "Default")
      (node (ref "GREEN_76") (pin "12") (pinfunction "OUT7_12") (pintype "bidirectional"))
      (node (ref "U$1") (pin "GRN_67") (pinfunction "GRN_67_GRN_67") (pintype "bidirectional"))
    )
    (net (code "131") (name "/GRN_70") (class "Default")
      (node (ref "GREEN_76") (pin "13") (pinfunction "OUT8_13") (pintype "bidirectional"))
      (node (ref "U$1") (pin "GRN_70") (pinfunction "GRN_70_GRN_70") (pintype "bidirectional"))
    )
    (net (code "132") (name "/GRN_71") (class "Default")
      (node (ref "GREEN_76") (pin "14") (pinfunction "OUT9_14") (pintype "bidirectional"))
      (node (ref "U$1") (pin "GRN_71") (pinfunction "GRN_71_GRN_71") (pintype "bidirectional"))
    )
    (net (code "133") (name "/GRN_72") (class "Default")
      (node (ref "GREEN_76") (pin "15") (pinfunction "OUT10_15") (pintype "bidirectional"))
      (node (ref "U$1") (pin "GRN_72") (pinfunction "GRN_72_GRN_72") (pintype "bidirectional"))
    )
    (net (code "134") (name "/GRN_73") (class "Default")
      (node (ref "GREEN_76") (pin "16") (pinfunction "OUT11_16") (pintype "bidirectional"))
      (node (ref "U$1") (pin "GRN_73") (pinfunction "GRN_73_GRN_73") (pintype "bidirectional"))
    )
    (net (code "135") (name "/GRN_74") (class "Default")
      (node (ref "GREEN_76") (pin "17") (pinfunction "OUT12_17") (pintype "bidirectional"))
      (node (ref "U$1") (pin "GRN_74") (pinfunction "GRN_74_GRN_74") (pintype "bidirectional"))
    )
    (net (code "136") (name "/GRN_75") (class "Default")
      (node (ref "GREEN_76") (pin "18") (pinfunction "OUT13_18") (pintype "bidirectional"))
      (node (ref "U$1") (pin "GRN_75") (pinfunction "GRN_75_GRN_75") (pintype "bidirectional"))
    )
    (net (code "137") (name "/GRN_76") (class "Default")
      (node (ref "GREEN_76") (pin "19") (pinfunction "OUT14_19") (pintype "bidirectional"))
      (node (ref "U$1") (pin "GRN_76") (pinfunction "GRN_76_GRN_76") (pintype "bidirectional"))
    )
    (net (code "138") (name "/GRN_76_DATA") (class "Default")
      (node (ref "GREEN_54") (pin "22") (pinfunction "SDO/DAO_22") (pintype "bidirectional"))
      (node (ref "GREEN_76") (pin "2") (pinfunction "SDI/DAI_2") (pintype "bidirectional"))
    )
    (net (code "139") (name "/GRN_77") (class "Default")
      (node (ref "GREEN_76") (pin "20") (pinfunction "OUT15_20") (pintype "bidirectional"))
      (node (ref "U$1") (pin "GRN_77") (pinfunction "GRN_77_GRN_77") (pintype "bidirectional"))
    )
    (net (code "140") (name "/GRN_OUT") (class "Default")
      (node (ref "GREEN_76") (pin "22") (pinfunction "SDO/DAO_22") (pintype "bidirectional"))
      (node (ref "RED_10") (pin "2") (pinfunction "SDI/DAI_2") (pintype "bidirectional"))
    )
    (net (code "141") (name "/LATCH") (class "Default")
      (node (ref "BLU_10") (pin "4") (pinfunction "LE/LAT_4") (pintype "bidirectional"))
      (node (ref "BLU_32") (pin "4") (pinfunction "LE/LAT_4") (pintype "bidirectional"))
      (node (ref "BLU_54") (pin "4") (pinfunction "LE/LAT_4") (pintype "bidirectional"))
      (node (ref "BLU_76") (pin "4") (pinfunction "LE/LAT_4") (pintype "bidirectional"))
      (node (ref "GREEN_10") (pin "4") (pinfunction "LE/LAT_4") (pintype "bidirectional"))
      (node (ref "GREEN_32") (pin "4") (pinfunction "LE/LAT_4") (pintype "bidirectional"))
      (node (ref "GREEN_54") (pin "4") (pinfunction "LE/LAT_4") (pintype "bidirectional"))
      (node (ref "GREEN_76") (pin "4") (pinfunction "LE/LAT_4") (pintype "bidirectional"))
      (node (ref "RED_10") (pin "4") (pinfunction "LE/LAT_4") (pintype "bidirectional"))
      (node (ref "RED_32") (pin "4") (pinfunction "LE/LAT_4") (pintype "bidirectional"))
      (node (ref "RED_54") (pin "4") (pinfunction "LE/LAT_4") (pintype "bidirectional"))
      (node (ref "RED_76") (pin "4") (pinfunction "LE/LAT_4") (pintype "bidirectional"))
      (node (ref "SV1") (pin "3") (pinfunction "3_3") (pintype "passive"))
    )
    (net (code "142") (name "/RED_00") (class "Default")
      (node (ref "RED_10") (pin "5") (pinfunction "OUT0_5") (pintype "bidirectional"))
      (node (ref "U$1") (pin "RED_00") (pinfunction "RED_00_RED_00") (pintype "bidirectional"))
    )
    (net (code "143") (name "/RED_01") (class "Default")
      (node (ref "RED_10") (pin "6") (pinfunction "OUT1_6") (pintype "bidirectional"))
      (node (ref "U$1") (pin "RED_01") (pinfunction "RED_01_RED_01") (pintype "bidirectional"))
    )
    (net (code "144") (name "/RED_02") (class "Default")
      (node (ref "RED_10") (pin "7") (pinfunction "OUT2_7") (pintype "bidirectional"))
      (node (ref "U$1") (pin "RED_02") (pinfunction "RED_02_RED_02") (pintype "bidirectional"))
    )
    (net (code "145") (name "/RED_03") (class "Default")
      (node (ref "RED_10") (pin "8") (pinfunction "OUT3_8") (pintype "bidirectional"))
      (node (ref "U$1") (pin "RED_03") (pinfunction "RED_03_RED_03") (pintype "bidirectional"))
    )
    (net (code "146") (name "/RED_04") (class "Default")
      (node (ref "RED_10") (pin "9") (pinfunction "OUT4_9") (pintype "bidirectional"))
      (node (ref "U$1") (pin "RED_04") (pinfunction "RED_04_RED_04") (pintype "bidirectional"))
    )
    (net (code "147") (name "/RED_05") (class "Default")
      (node (ref "RED_10") (pin "10") (pinfunction "OUT5_10") (pintype "bidirectional"))
      (node (ref "U$1") (pin "RED_05") (pinfunction "RED_05_RED_05") (pintype "bidirectional"))
    )
    (net (code "148") (name "/RED_06") (class "Default")
      (node (ref "RED_10") (pin "11") (pinfunction "OUT6_11") (pintype "bidirectional"))
      (node (ref "U$1") (pin "RED_06") (pinfunction "RED_06_RED_06") (pintype "bidirectional"))
    )
    (net (code "149") (name "/RED_07") (class "Default")
      (node (ref "RED_10") (pin "12") (pinfunction "OUT7_12") (pintype "bidirectional"))
      (node (ref "U$1") (pin "RED_07") (pinfunction "RED_07_RED_07") (pintype "bidirectional"))
    )
    (net (code "150") (name "/RED_10") (class "Default")
      (node (ref "RED_10") (pin "13") (pinfunction "OUT8_13") (pintype "bidirectional"))
      (node (ref "U$1") (pin "RED_10") (pinfunction "RED_10_RED_10") (pintype "bidirectional"))
    )
    (net (code "151") (name "/RED_11") (class "Default")
      (node (ref "RED_10") (pin "14") (pinfunction "OUT9_14") (pintype "bidirectional"))
      (node (ref "U$1") (pin "RED_11") (pinfunction "RED_11_RED_11") (pintype "bidirectional"))
    )
    (net (code "152") (name "/RED_12") (class "Default")
      (node (ref "RED_10") (pin "15") (pinfunction "OUT10_15") (pintype "bidirectional"))
      (node (ref "U$1") (pin "RED_12") (pinfunction "RED_12_RED_12") (pintype "bidirectional"))
    )
    (net (code "153") (name "/RED_13") (class "Default")
      (node (ref "RED_10") (pin "16") (pinfunction "OUT11_16") (pintype "bidirectional"))
      (node (ref "U$1") (pin "RED_13") (pinfunction "RED_13_RED_13") (pintype "bidirectional"))
    )
    (net (code "154") (name "/RED_14") (class "Default")
      (node (ref "RED_10") (pin "17") (pinfunction "OUT12_17") (pintype "bidirectional"))
      (node (ref "U$1") (pin "RED_14") (pinfunction "RED_14_RED_14") (pintype "bidirectional"))
    )
    (net (code "155") (name "/RED_15") (class "Default")
      (node (ref "RED_10") (pin "18") (pinfunction "OUT13_18") (pintype "bidirectional"))
      (node (ref "U$1") (pin "RED_15") (pinfunction "RED_15_RED_15") (pintype "bidirectional"))
    )
    (net (code "156") (name "/RED_16") (class "Default")
      (node (ref "RED_10") (pin "19") (pinfunction "OUT14_19") (pintype "bidirectional"))
      (node (ref "U$1") (pin "RED_16") (pinfunction "RED_16_RED_16") (pintype "bidirectional"))
    )
    (net (code "157") (name "/RED_17") (class "Default")
      (node (ref "RED_10") (pin "20") (pinfunction "OUT15_20") (pintype "bidirectional"))
      (node (ref "U$1") (pin "RED_17") (pinfunction "RED_17_RED_17") (pintype "bidirectional"))
    )
    (net (code "158") (name "/RED_20") (class "Default")
      (node (ref "RED_32") (pin "5") (pinfunction "OUT0_5") (pintype "bidirectional"))
      (node (ref "U$1") (pin "RED_20") (pinfunction "RED_20_RED_20") (pintype "bidirectional"))
    )
    (net (code "159") (name "/RED_21") (class "Default")
      (node (ref "RED_32") (pin "6") (pinfunction "OUT1_6") (pintype "bidirectional"))
      (node (ref "U$1") (pin "RED_21") (pinfunction "RED_21_RED_21") (pintype "bidirectional"))
    )
    (net (code "160") (name "/RED_22") (class "Default")
      (node (ref "RED_32") (pin "7") (pinfunction "OUT2_7") (pintype "bidirectional"))
      (node (ref "U$1") (pin "RED_22") (pinfunction "RED_22_RED_22") (pintype "bidirectional"))
    )
    (net (code "161") (name "/RED_23") (class "Default")
      (node (ref "RED_32") (pin "8") (pinfunction "OUT3_8") (pintype "bidirectional"))
      (node (ref "U$1") (pin "RED_23") (pinfunction "RED_23_RED_23") (pintype "bidirectional"))
    )
    (net (code "162") (name "/RED_24") (class "Default")
      (node (ref "RED_32") (pin "9") (pinfunction "OUT4_9") (pintype "bidirectional"))
      (node (ref "U$1") (pin "RED_24") (pinfunction "RED_24_RED_24") (pintype "bidirectional"))
    )
    (net (code "163") (name "/RED_25") (class "Default")
      (node (ref "RED_32") (pin "10") (pinfunction "OUT5_10") (pintype "bidirectional"))
      (node (ref "U$1") (pin "RED_25") (pinfunction "RED_25_RED_25") (pintype "bidirectional"))
    )
    (net (code "164") (name "/RED_26") (class "Default")
      (node (ref "RED_32") (pin "11") (pinfunction "OUT6_11") (pintype "bidirectional"))
      (node (ref "U$1") (pin "RED_26") (pinfunction "RED_26_RED_26") (pintype "bidirectional"))
    )
    (net (code "165") (name "/RED_27") (class "Default")
      (node (ref "RED_32") (pin "12") (pinfunction "OUT7_12") (pintype "bidirectional"))
      (node (ref "U$1") (pin "RED_27") (pinfunction "RED_27_RED_27") (pintype "bidirectional"))
    )
    (net (code "166") (name "/RED_30") (class "Default")
      (node (ref "RED_32") (pin "13") (pinfunction "OUT8_13") (pintype "bidirectional"))
      (node (ref "U$1") (pin "RED_30") (pinfunction "RED_30_RED_30") (pintype "bidirectional"))
    )
    (net (code "167") (name "/RED_31") (class "Default")
      (node (ref "RED_32") (pin "14") (pinfunction "OUT9_14") (pintype "bidirectional"))
      (node (ref "U$1") (pin "RED_31") (pinfunction "RED_31_RED_31") (pintype "bidirectional"))
    )
    (net (code "168") (name "/RED_32") (class "Default")
      (node (ref "RED_32") (pin "15") (pinfunction "OUT10_15") (pintype "bidirectional"))
      (node (ref "U$1") (pin "RED_32") (pinfunction "RED_32_RED_32") (pintype "bidirectional"))
    )
    (net (code "169") (name "/RED_32_DATA") (class "Default")
      (node (ref "RED_10") (pin "22") (pinfunction "SDO/DAO_22") (pintype "bidirectional"))
      (node (ref "RED_32") (pin "2") (pinfunction "SDI/DAI_2") (pintype "bidirectional"))
    )
    (net (code "170") (name "/RED_33") (class "Default")
      (node (ref "RED_32") (pin "16") (pinfunction "OUT11_16") (pintype "bidirectional"))
      (node (ref "U$1") (pin "RED_33") (pinfunction "RED_33_RED_33") (pintype "bidirectional"))
    )
    (net (code "171") (name "/RED_34") (class "Default")
      (node (ref "RED_32") (pin "17") (pinfunction "OUT12_17") (pintype "bidirectional"))
      (node (ref "U$1") (pin "RED_34") (pinfunction "RED_34_RED_34") (pintype "bidirectional"))
    )
    (net (code "172") (name "/RED_35") (class "Default")
      (node (ref "RED_32") (pin "18") (pinfunction "OUT13_18") (pintype "bidirectional"))
      (node (ref "U$1") (pin "RED_35") (pinfunction "RED_35_RED_35") (pintype "bidirectional"))
    )
    (net (code "173") (name "/RED_36") (class "Default")
      (node (ref "RED_32") (pin "19") (pinfunction "OUT14_19") (pintype "bidirectional"))
      (node (ref "U$1") (pin "RED_36") (pinfunction "RED_36_RED_36") (pintype "bidirectional"))
    )
    (net (code "174") (name "/RED_37") (class "Default")
      (node (ref "RED_32") (pin "20") (pinfunction "OUT15_20") (pintype "bidirectional"))
      (node (ref "U$1") (pin "RED_37") (pinfunction "RED_37_RED_37") (pintype "bidirectional"))
    )
    (net (code "175") (name "/RED_40") (class "Default")
      (node (ref "RED_54") (pin "5") (pinfunction "OUT0_5") (pintype "bidirectional"))
      (node (ref "U$1") (pin "RED_40") (pinfunction "RED_40_RED_40") (pintype "bidirectional"))
    )
    (net (code "176") (name "/RED_41") (class "Default")
      (node (ref "RED_54") (pin "6") (pinfunction "OUT1_6") (pintype "bidirectional"))
      (node (ref "U$1") (pin "RED_41") (pinfunction "RED_41_RED_41") (pintype "bidirectional"))
    )
    (net (code "177") (name "/RED_42") (class "Default")
      (node (ref "RED_54") (pin "7") (pinfunction "OUT2_7") (pintype "bidirectional"))
      (node (ref "U$1") (pin "RED_42") (pinfunction "RED_42_RED_42") (pintype "bidirectional"))
    )
    (net (code "178") (name "/RED_43") (class "Default")
      (node (ref "RED_54") (pin "8") (pinfunction "OUT3_8") (pintype "bidirectional"))
      (node (ref "U$1") (pin "RED_43") (pinfunction "RED_43_RED_43") (pintype "bidirectional"))
    )
    (net (code "179") (name "/RED_44") (class "Default")
      (node (ref "RED_54") (pin "9") (pinfunction "OUT4_9") (pintype "bidirectional"))
      (node (ref "U$1") (pin "RED_44") (pinfunction "RED_44_RED_44") (pintype "bidirectional"))
    )
    (net (code "180") (name "/RED_45") (class "Default")
      (node (ref "RED_54") (pin "10") (pinfunction "OUT5_10") (pintype "bidirectional"))
      (node (ref "U$1") (pin "RED_45") (pinfunction "RED_45_RED_45") (pintype "bidirectional"))
    )
    (net (code "181") (name "/RED_46") (class "Default")
      (node (ref "RED_54") (pin "11") (pinfunction "OUT6_11") (pintype "bidirectional"))
      (node (ref "U$1") (pin "RED_46") (pinfunction "RED_46_RED_46") (pintype "bidirectional"))
    )
    (net (code "182") (name "/RED_47") (class "Default")
      (node (ref "RED_54") (pin "12") (pinfunction "OUT7_12") (pintype "bidirectional"))
      (node (ref "U$1") (pin "RED_47") (pinfunction "RED_47_RED_47") (pintype "bidirectional"))
    )
    (net (code "183") (name "/RED_50") (class "Default")
      (node (ref "RED_54") (pin "13") (pinfunction "OUT8_13") (pintype "bidirectional"))
      (node (ref "U$1") (pin "RED_50") (pinfunction "RED_50_RED_50") (pintype "bidirectional"))
    )
    (net (code "184") (name "/RED_51") (class "Default")
      (node (ref "RED_54") (pin "14") (pinfunction "OUT9_14") (pintype "bidirectional"))
      (node (ref "U$1") (pin "RED_51") (pinfunction "RED_51_RED_51") (pintype "bidirectional"))
    )
    (net (code "185") (name "/RED_52") (class "Default")
      (node (ref "RED_54") (pin "15") (pinfunction "OUT10_15") (pintype "bidirectional"))
      (node (ref "U$1") (pin "RED_52") (pinfunction "RED_52_RED_52") (pintype "bidirectional"))
    )
    (net (code "186") (name "/RED_53") (class "Default")
      (node (ref "RED_54") (pin "16") (pinfunction "OUT11_16") (pintype "bidirectional"))
      (node (ref "U$1") (pin "RED_53") (pinfunction "RED_53_RED_53") (pintype "bidirectional"))
    )
    (net (code "187") (name "/RED_54") (class "Default")
      (node (ref "RED_54") (pin "17") (pinfunction "OUT12_17") (pintype "bidirectional"))
      (node (ref "U$1") (pin "RED_54") (pinfunction "RED_54_RED_54") (pintype "bidirectional"))
    )
    (net (code "188") (name "/RED_54_DATA") (class "Default")
      (node (ref "RED_32") (pin "22") (pinfunction "SDO/DAO_22") (pintype "bidirectional"))
      (node (ref "RED_54") (pin "2") (pinfunction "SDI/DAI_2") (pintype "bidirectional"))
    )
    (net (code "189") (name "/RED_55") (class "Default")
      (node (ref "RED_54") (pin "18") (pinfunction "OUT13_18") (pintype "bidirectional"))
      (node (ref "U$1") (pin "RED_55") (pinfunction "RED_55_RED_55") (pintype "bidirectional"))
    )
    (net (code "190") (name "/RED_56") (class "Default")
      (node (ref "RED_54") (pin "19") (pinfunction "OUT14_19") (pintype "bidirectional"))
      (node (ref "U$1") (pin "RED_56") (pinfunction "RED_56_RED_56") (pintype "bidirectional"))
    )
    (net (code "191") (name "/RED_57") (class "Default")
      (node (ref "RED_54") (pin "20") (pinfunction "OUT15_20") (pintype "bidirectional"))
      (node (ref "U$1") (pin "RED_57") (pinfunction "RED_57_RED_57") (pintype "bidirectional"))
    )
    (net (code "192") (name "/RED_60") (class "Default")
      (node (ref "RED_76") (pin "5") (pinfunction "OUT0_5") (pintype "bidirectional"))
      (node (ref "U$1") (pin "RED_60") (pinfunction "RED_60_RED_60") (pintype "bidirectional"))
    )
    (net (code "193") (name "/RED_61") (class "Default")
      (node (ref "RED_76") (pin "6") (pinfunction "OUT1_6") (pintype "bidirectional"))
      (node (ref "U$1") (pin "RED_61") (pinfunction "RED_61_RED_61") (pintype "bidirectional"))
    )
    (net (code "194") (name "/RED_62") (class "Default")
      (node (ref "RED_76") (pin "7") (pinfunction "OUT2_7") (pintype "bidirectional"))
      (node (ref "U$1") (pin "RED_62") (pinfunction "RED_62_RED_62") (pintype "bidirectional"))
    )
    (net (code "195") (name "/RED_63") (class "Default")
      (node (ref "RED_76") (pin "8") (pinfunction "OUT3_8") (pintype "bidirectional"))
      (node (ref "U$1") (pin "RED_63") (pinfunction "RED_63_RED_63") (pintype "bidirectional"))
    )
    (net (code "196") (name "/RED_64") (class "Default")
      (node (ref "RED_76") (pin "9") (pinfunction "OUT4_9") (pintype "bidirectional"))
      (node (ref "U$1") (pin "RED_64") (pinfunction "RED_64_RED_64") (pintype "bidirectional"))
    )
    (net (code "197") (name "/RED_65") (class "Default")
      (node (ref "RED_76") (pin "10") (pinfunction "OUT5_10") (pintype "bidirectional"))
      (node (ref "U$1") (pin "RED_65") (pinfunction "RED_65_RED_65") (pintype "bidirectional"))
    )
    (net (code "198") (name "/RED_66") (class "Default")
      (node (ref "RED_76") (pin "11") (pinfunction "OUT6_11") (pintype "bidirectional"))
      (node (ref "U$1") (pin "RED_66") (pinfunction "RED_66_RED_66") (pintype "bidirectional"))
    )
    (net (code "199") (name "/RED_67") (class "Default")
      (node (ref "RED_76") (pin "12") (pinfunction "OUT7_12") (pintype "bidirectional"))
      (node (ref "U$1") (pin "RED_67") (pinfunction "RED_67_RED_67") (pintype "bidirectional"))
    )
    (net (code "200") (name "/RED_70") (class "Default")
      (node (ref "RED_76") (pin "13") (pinfunction "OUT8_13") (pintype "bidirectional"))
      (node (ref "U$1") (pin "RED_70") (pinfunction "RED_70_RED_70") (pintype "bidirectional"))
    )
    (net (code "201") (name "/RED_71") (class "Default")
      (node (ref "RED_76") (pin "14") (pinfunction "OUT9_14") (pintype "bidirectional"))
      (node (ref "U$1") (pin "RED_71") (pinfunction "RED_71_RED_71") (pintype "bidirectional"))
    )
    (net (code "202") (name "/RED_72") (class "Default")
      (node (ref "RED_76") (pin "15") (pinfunction "OUT10_15") (pintype "bidirectional"))
      (node (ref "U$1") (pin "RED_72") (pinfunction "RED_72_RED_72") (pintype "bidirectional"))
    )
    (net (code "203") (name "/RED_73") (class "Default")
      (node (ref "RED_76") (pin "16") (pinfunction "OUT11_16") (pintype "bidirectional"))
      (node (ref "U$1") (pin "RED_73") (pinfunction "RED_73_RED_73") (pintype "bidirectional"))
    )
    (net (code "204") (name "/RED_74") (class "Default")
      (node (ref "RED_76") (pin "17") (pinfunction "OUT12_17") (pintype "bidirectional"))
      (node (ref "U$1") (pin "RED_74") (pinfunction "RED_74_RED_74") (pintype "bidirectional"))
    )
    (net (code "205") (name "/RED_75") (class "Default")
      (node (ref "RED_76") (pin "18") (pinfunction "OUT13_18") (pintype "bidirectional"))
      (node (ref "U$1") (pin "RED_75") (pinfunction "RED_75_RED_75") (pintype "bidirectional"))
    )
    (net (code "206") (name "/RED_76") (class "Default")
      (node (ref "RED_76") (pin "19") (pinfunction "OUT14_19") (pintype "bidirectional"))
      (node (ref "U$1") (pin "RED_76") (pinfunction "RED_76_RED_76") (pintype "bidirectional"))
    )
    (net (code "207") (name "/RED_76_DATA") (class "Default")
      (node (ref "RED_54") (pin "22") (pinfunction "SDO/DAO_22") (pintype "bidirectional"))
      (node (ref "RED_76") (pin "2") (pinfunction "SDI/DAI_2") (pintype "bidirectional"))
    )
    (net (code "208") (name "/RED_77") (class "Default")
      (node (ref "RED_76") (pin "20") (pinfunction "OUT15_20") (pintype "bidirectional"))
      (node (ref "U$1") (pin "RED_77") (pinfunction "RED_77_RED_77") (pintype "bidirectional"))
    )
    (net (code "210") (name "GND") (class "Default")
      (node (ref "BLU_10") (pin "1") (pinfunction "GND_1") (pintype "bidirectional"))
      (node (ref "BLU_32") (pin "1") (pinfunction "GND_1") (pintype "bidirectional"))
      (node (ref "BLU_54") (pin "1") (pinfunction "GND_1") (pintype "bidirectional"))
      (node (ref "BLU_76") (pin "1") (pinfunction "GND_1") (pintype "bidirectional"))
      (node (ref "C1") (pin "2") (pinfunction "2_2") (pintype "passive"))
      (node (ref "C10") (pin "2") (pinfunction "2_2") (pintype "passive"))
      (node (ref "C11") (pin "2") (pinfunction "2_2") (pintype "passive"))
      (node (ref "C12") (pin "2") (pinfunction "2_2") (pintype "passive"))
      (node (ref "C2") (pin "2") (pinfunction "2_2") (pintype "passive"))
      (node (ref "C3") (pin "2") (pinfunction "2_2") (pintype "passive"))
      (node (ref "C4") (pin "2") (pinfunction "2_2") (pintype "passive"))
      (node (ref "C5") (pin "2") (pinfunction "2_2") (pintype "passive"))
      (node (ref "C6") (pin "2") (pinfunction "2_2") (pintype "passive"))
      (node (ref "C7") (pin "2") (pinfunction "2_2") (pintype "passive"))
      (node (ref "C8") (pin "2") (pinfunction "2_2") (pintype "passive"))
      (node (ref "C9") (pin "2") (pinfunction "2_2") (pintype "passive"))
      (node (ref "GREEN_10") (pin "1") (pinfunction "GND_1") (pintype "bidirectional"))
      (node (ref "GREEN_32") (pin "1") (pinfunction "GND_1") (pintype "bidirectional"))
      (node (ref "GREEN_54") (pin "1") (pinfunction "GND_1") (pintype "bidirectional"))
      (node (ref "GREEN_76") (pin "1") (pinfunction "GND_1") (pintype "bidirectional"))
      (node (ref "R1") (pin "1") (pinfunction "1_1") (pintype "passive"))
      (node (ref "R10") (pin "1") (pinfunction "1_1") (pintype "passive"))
      (node (ref "R11") (pin "1") (pinfunction "1_1") (pintype "passive"))
      (node (ref "R12") (pin "1") (pinfunction "1_1") (pintype "passive"))
      (node (ref "R2") (pin "1") (pinfunction "1_1") (pintype "passive"))
      (node (ref "R3") (pin "1") (pinfunction "1_1") (pintype "passive"))
      (node (ref "R4") (pin "1") (pinfunction "1_1") (pintype "passive"))
      (node (ref "R5") (pin "1") (pinfunction "1_1") (pintype "passive"))
      (node (ref "R6") (pin "1") (pinfunction "1_1") (pintype "passive"))
      (node (ref "R7") (pin "1") (pinfunction "1_1") (pintype "passive"))
      (node (ref "R8") (pin "1") (pinfunction "1_1") (pintype "passive"))
      (node (ref "R9") (pin "1") (pinfunction "1_1") (pintype "passive"))
      (node (ref "RED_10") (pin "1") (pinfunction "GND_1") (pintype "bidirectional"))
      (node (ref "RED_32") (pin "1") (pinfunction "GND_1") (pintype "bidirectional"))
      (node (ref "RED_54") (pin "1") (pinfunction "GND_1") (pintype "bidirectional"))
      (node (ref "RED_76") (pin "1") (pinfunction "GND_1") (pintype "bidirectional"))
      (node (ref "SV1") (pin "1") (pinfunction "1_1") (pintype "passive"))
      (node (ref "SV1") (pin "2") (pinfunction "2_2") (pintype "passive"))
    )
    (net (code "211") (name "Net-(BLU_10-REXT)") (class "Default")
      (node (ref "BLU_10") (pin "23") (pinfunction "REXT_23") (pintype "bidirectional"))
      (node (ref "R9") (pin "2") (pinfunction "2_2") (pintype "passive"))
    )
    (net (code "212") (name "Net-(BLU_32-REXT)") (class "Default")
      (node (ref "BLU_32") (pin "23") (pinfunction "REXT_23") (pintype "bidirectional"))
      (node (ref "R10") (pin "2") (pinfunction "2_2") (pintype "passive"))
    )
    (net (code "213") (name "Net-(BLU_54-REXT)") (class "Default")
      (node (ref "BLU_54") (pin "23") (pinfunction "REXT_23") (pintype "bidirectional"))
      (node (ref "R11") (pin "2") (pinfunction "2_2") (pintype "passive"))
    )
    (net (code "214") (name "Net-(BLU_76-REXT)") (class "Default")
      (node (ref "BLU_76") (pin "23") (pinfunction "REXT_23") (pintype "bidirectional"))
      (node (ref "R12") (pin "2") (pinfunction "2_2") (pintype "passive"))
    )
    (net (code "215") (name "Net-(GREEN_10-REXT)") (class "Default")
      (node (ref "GREEN_10") (pin "23") (pinfunction "REXT_23") (pintype "bidirectional"))
      (node (ref "R5") (pin "2") (pinfunction "2_2") (pintype "passive"))
    )
    (net (code "216") (name "Net-(GREEN_32-REXT)") (class "Default")
      (node (ref "GREEN_32") (pin "23") (pinfunction "REXT_23") (pintype "bidirectional"))
      (node (ref "R6") (pin "2") (pinfunction "2_2") (pintype "passive"))
    )
    (net (code "217") (name "Net-(GREEN_54-REXT)") (class "Default")
      (node (ref "GREEN_54") (pin "23") (pinfunction "REXT_23") (pintype "bidirectional"))
      (node (ref "R7") (pin "2") (pinfunction "2_2") (pintype "passive"))
    )
    (net (code "218") (name "Net-(GREEN_76-REXT)") (class "Default")
      (node (ref "GREEN_76") (pin "23") (pinfunction "REXT_23") (pintype "bidirectional"))
      (node (ref "R8") (pin "2") (pinfunction "2_2") (pintype "passive"))
    )
    (net (code "219") (name "Net-(RED_10-REXT)") (class "Default")
      (node (ref "R1") (pin "2") (pinfunction "2_2") (pintype "passive"))
      (node (ref "RED_10") (pin "23") (pinfunction "REXT_23") (pintype "bidirectional"))
    )
    (net (code "220") (name "Net-(RED_32-REXT)") (class "Default")
      (node (ref "R2") (pin "2") (pinfunction "2_2") (pintype "passive"))
      (node (ref "RED_32") (pin "23") (pinfunction "REXT_23") (pintype "bidirectional"))
    )
    (net (code "221") (name "Net-(RED_54-REXT)") (class "Default")
      (node (ref "R3") (pin "2") (pinfunction "2_2") (pintype "passive"))
      (node (ref "RED_54") (pin "23") (pinfunction "REXT_23") (pintype "bidirectional"))
    )
    (net (code "222") (name "Net-(RED_76-REXT)") (class "Default")
      (node (ref "R4") (pin "2") (pinfunction "2_2") (pintype "passive"))
      (node (ref "RED_76") (pin "23") (pinfunction "REXT_23") (pintype "bidirectional"))
    )
    (net (code "223") (name "VCC") (class "Default")
      (node (ref "BLU_10") (pin "24") (pinfunction "VDD_24") (pintype "bidirectional"))
      (node (ref "BLU_32") (pin "24") (pinfunction "VDD_24") (pintype "bidirectional"))
      (node (ref "BLU_54") (pin "24") (pinfunction "VDD_24") (pintype "bidirectional"))
      (node (ref "BLU_76") (pin "24") (pinfunction "VDD_24") (pintype "bidirectional"))
      (node (ref "C1") (pin "1") (pinfunction "1_1") (pintype "passive"))
      (node (ref "C10") (pin "1") (pinfunction "1_1") (pintype "passive"))
      (node (ref "C11") (pin "1") (pinfunction "1_1") (pintype "passive"))
      (node (ref "C12") (pin "1") (pinfunction "1_1") (pintype "passive"))
      (node (ref "C2") (pin "1") (pinfunction "1_1") (pintype "passive"))
      (node (ref "C3") (pin "1") (pinfunction "1_1") (pintype "passive"))
      (node (ref "C4") (pin "1") (pinfunction "1_1") (pintype "passive"))
      (node (ref "C5") (pin "1") (pinfunction "1_1") (pintype "passive"))
      (node (ref "C6") (pin "1") (pinfunction "1_1") (pintype "passive"))
      (node (ref "C7") (pin "1") (pinfunction "1_1") (pintype "passive"))
      (node (ref "C8") (pin "1") (pinfunction "1_1") (pintype "passive"))
      (node (ref "C9") (pin "1") (pinfunction "1_1") (pintype "passive"))
      (node (ref "GREEN_10") (pin "24") (pinfunction "VDD_24") (pintype "bidirectional"))
      (node (ref "GREEN_32") (pin "24") (pinfunction "VDD_24") (pintype "bidirectional"))
      (node (ref "GREEN_54") (pin "24") (pinfunction "VDD_24") (pintype "bidirectional"))
      (node (ref "GREEN_76") (pin "24") (pinfunction "VDD_24") (pintype "bidirectional"))
      (node (ref "RED_10") (pin "24") (pinfunction "VDD_24") (pintype "bidirectional"))
      (node (ref "RED_32") (pin "24") (pinfunction "VDD_24") (pintype "bidirectional"))
      (node (ref "RED_54") (pin "24") (pinfunction "VDD_24") (pintype "bidirectional"))
      (node (ref "RED_76") (pin "24") (pinfunction "VDD_24") (pintype "bidirectional"))
      (node (ref "SV1") (pin "12") (pinfunction "12_12") (pintype "passive"))
    )
    (net (code "224") (name "unconnected-(RED_76-SDO{slash}DAO-Pad22)") (class "Default")
      (node (ref "RED_76") (pin "22") (pinfunction "SDO/DAO_22") (pintype "bidirectional"))
    )
    (net (code "225") (name "unconnected-(SV1-Pad7)") (class "Default")
      (node (ref "SV1") (pin "7") (pinfunction "7_7") (pintype "passive"))
    )
    (net (code "226") (name "unconnected-(SV1-Pad8)") (class "Default")
      (node (ref "SV1") (pin "8") (pinfunction "8_8") (pintype "passive"))
    )
    (net (code "227") (name "unconnected-(SV1-Pad9)") (class "Default")
      (node (ref "SV1") (pin "9") (pinfunction "9_9") (pintype "passive"))
    )
    (net (code "228") (name "unconnected-(SV1-Pad10)") (class "Default")
      (node (ref "SV1") (pin "10") (pinfunction "10_10") (pintype "passive"))
    )
    (net (code "229") (name "unconnected-(SV1-Pad11)") (class "Default")
      (node (ref "SV1") (pin "11") (pinfunction "11_11") (pintype "passive"))
    )
    (net (code "230") (name "unconnected-(SV2-Pad1)") (class "Default")
      (node (ref "SV2") (pin "1") (pinfunction "1_1") (pintype "passive"))
    )
    (net (code "231") (name "unconnected-(SV2-Pad2)") (class "Default")
      (node (ref "SV2") (pin "2") (pinfunction "2_2") (pintype "passive"))
    )
    (net (code "232") (name "unconnected-(SV2-Pad3)") (class "Default")
      (node (ref "SV2") (pin "3") (pinfunction "3_3") (pintype "passive"))
    )
    (net (code "233") (name "unconnected-(SV2-Pad4)") (class "Default")
      (node (ref "SV2") (pin "4") (pinfunction "4_4") (pintype "passive"))
    )
    (net (code "234") (name "unconnected-(SV2-Pad5)") (class "Default")
      (node (ref "SV2") (pin "5") (pinfunction "5_5") (pintype "passive"))
    )
    (net (code "235") (name "unconnected-(SV2-Pad6)") (class "Default")
      (node (ref "SV2") (pin "6") (pinfunction "6_6") (pintype "passive"))
    )
    (net (code "236") (name "unconnected-(SV2-Pad7)") (class "Default")
      (node (ref "SV2") (pin "7") (pinfunction "7_7") (pintype "passive"))
    )
    (net (code "237") (name "unconnected-(SV2-Pad8)") (class "Default")
      (node (ref "SV2") (pin "8") (pinfunction "8_8") (pintype "passive"))
    )
  )
)
